# Solder_practice.net
KiCad netlist of a schematic drawn in EasyEDA
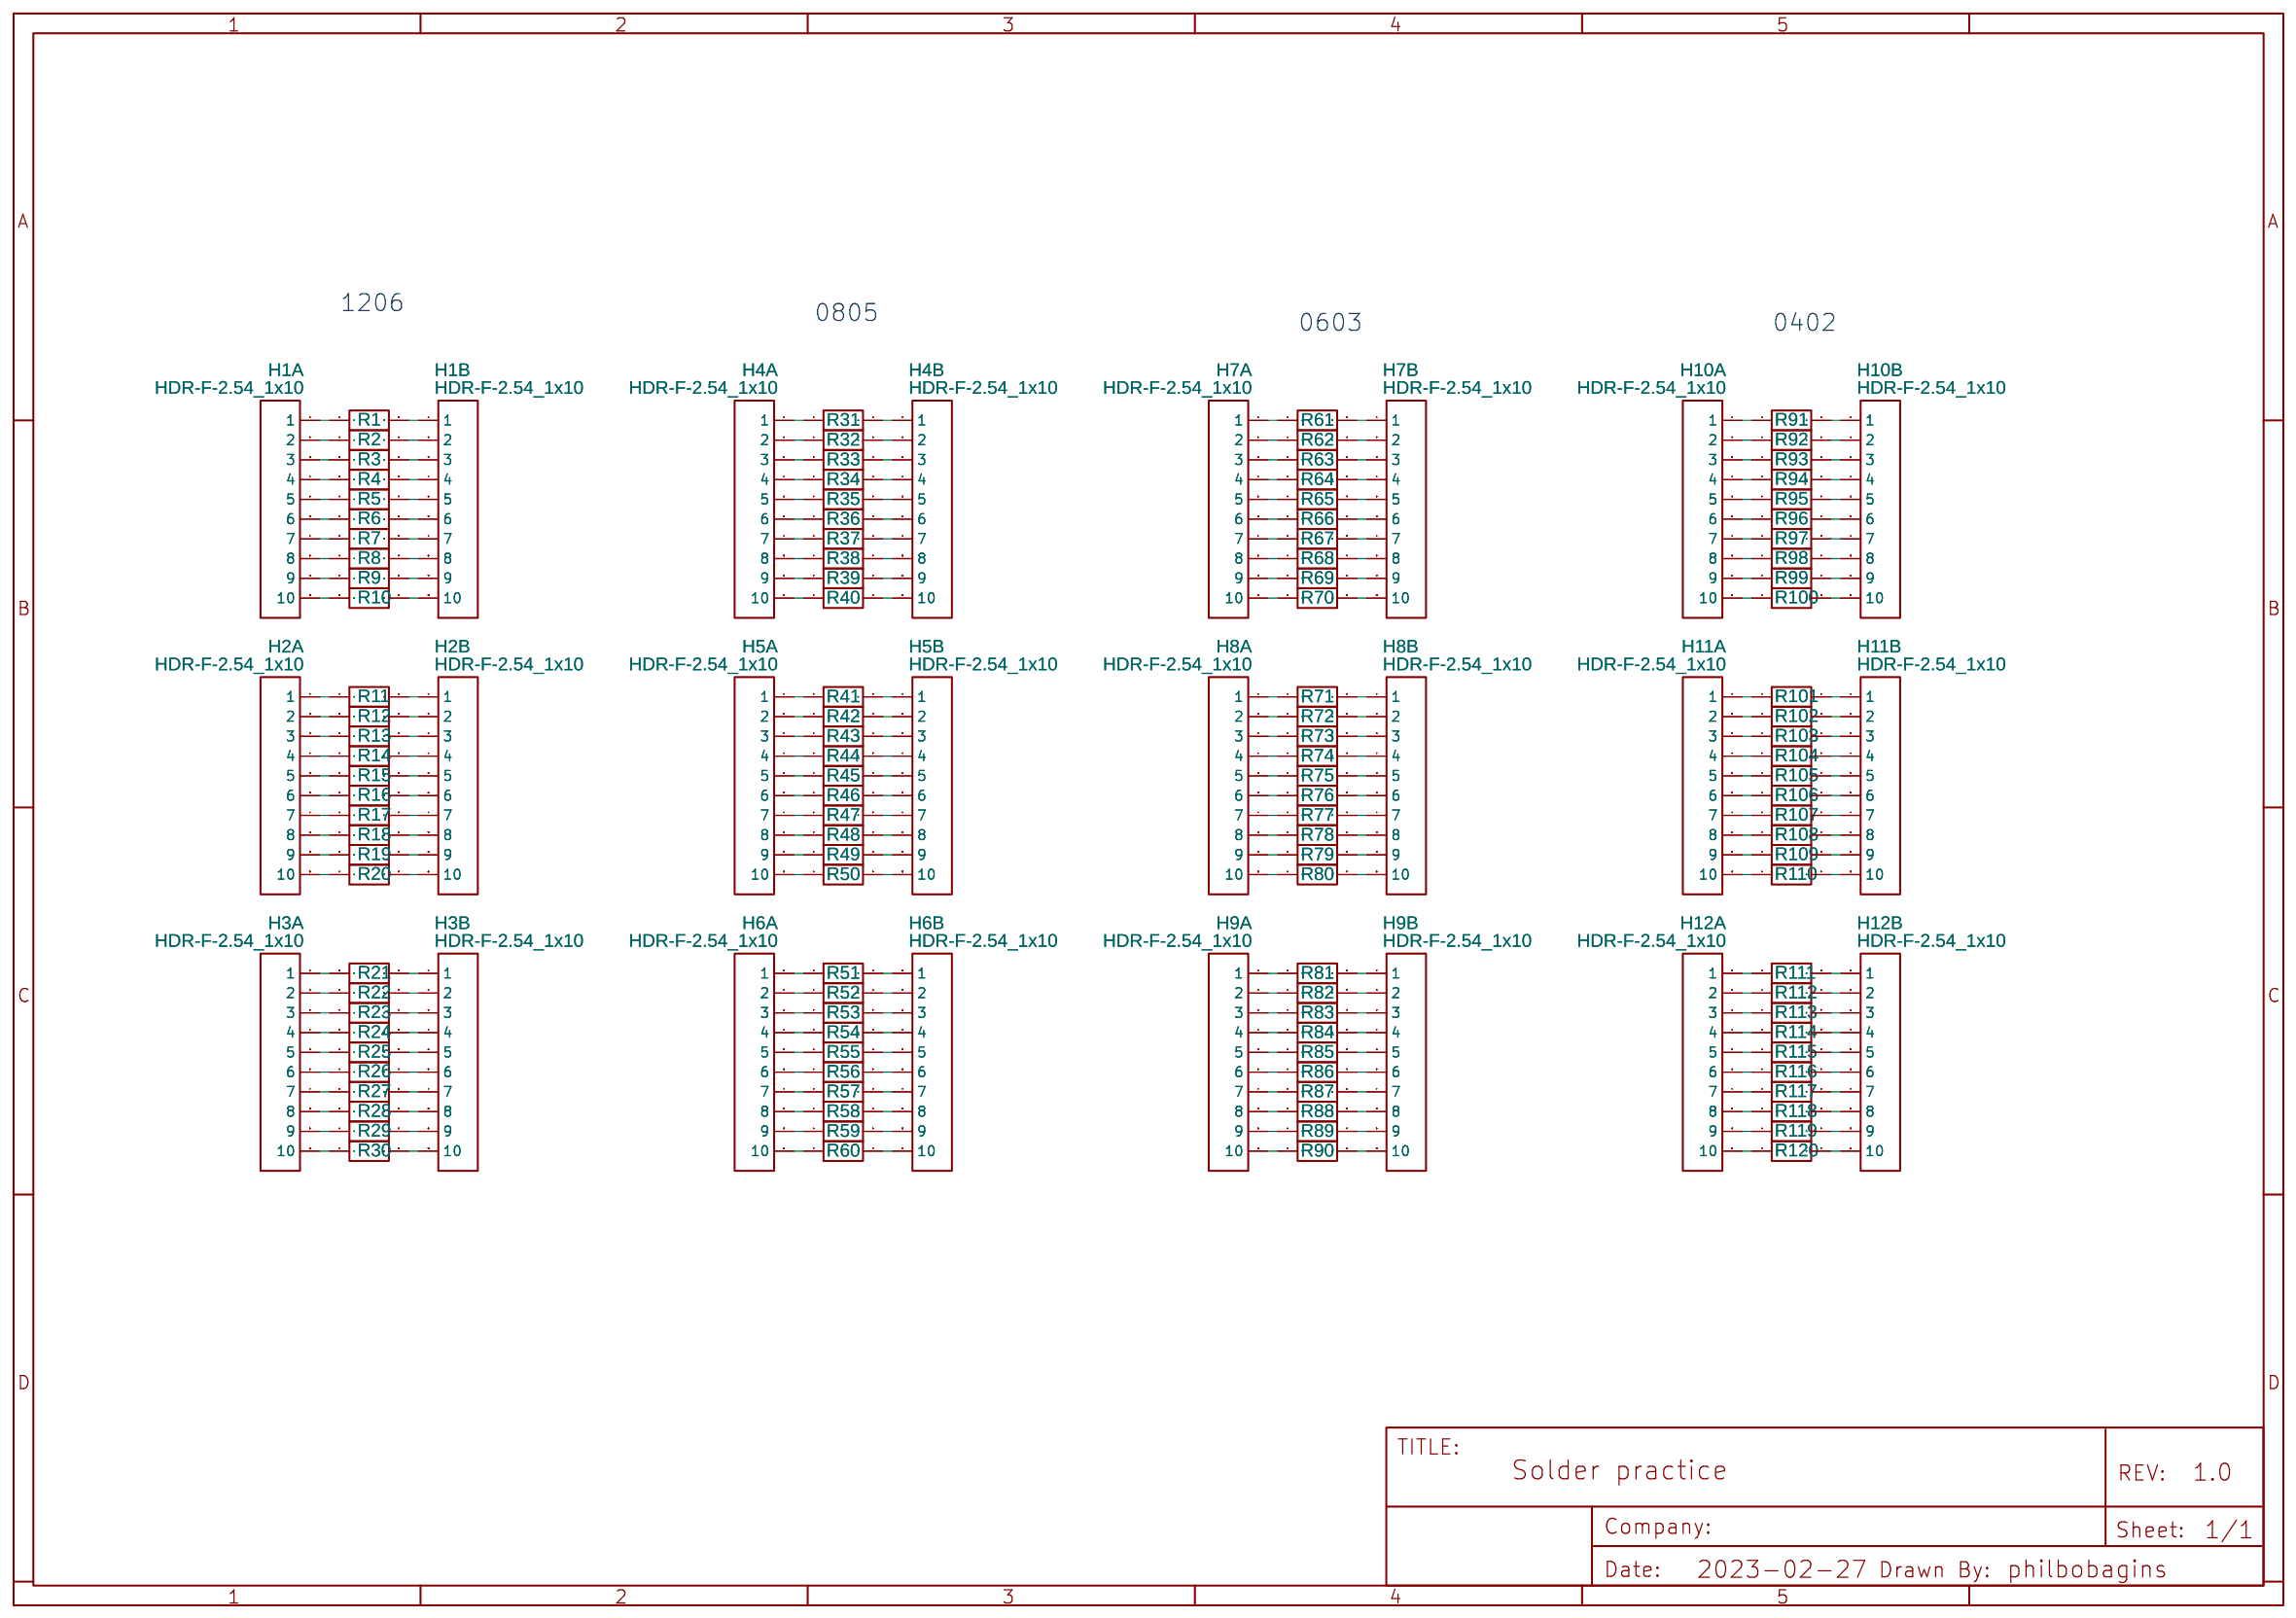
[diagram p0: schematic sheet]

(export (version "E")
  (design (tool "Eeschema 10.0.6"))
  (components
    (comp (ref "H1A")
      (value "HDR-F-2.54_1x10")
      (fields (field (name "BOM_Supplier Part") "C35445"))
      (libsource (lib "") (part "HDR-F-2.54_1x10"))
    )
    (comp (ref "H1B")
      (value "HDR-F-2.54_1x10")
      (fields (field (name "BOM_Supplier Part") "C35445"))
      (libsource (lib "") (part "HDR-F-2.54_1x10_20"))
    )
    (comp (ref "H2A")
      (value "HDR-F-2.54_1x10")
      (fields (field (name "BOM_Supplier Part") "C35445"))
      (libsource (lib "") (part "HDR-F-2.54_1x10_6"))
    )
    (comp (ref "H2B")
      (value "HDR-F-2.54_1x10")
      (fields (field (name "BOM_Supplier Part") "C35445"))
      (libsource (lib "") (part "HDR-F-2.54_1x10_19"))
    )
    (comp (ref "H3A")
      (value "HDR-F-2.54_1x10")
      (fields (field (name "BOM_Supplier Part") "C35445"))
      (libsource (lib "") (part "HDR-F-2.54_1x10_1"))
    )
    (comp (ref "H3B")
      (value "HDR-F-2.54_1x10")
      (fields (field (name "BOM_Supplier Part") "C35445"))
      (libsource (lib "") (part "HDR-F-2.54_1x10_8"))
    )
    (comp (ref "H4A")
      (value "HDR-F-2.54_1x10")
      (fields (field (name "BOM_Supplier Part") "C35445"))
      (libsource (lib "") (part "HDR-F-2.54_1x10_2"))
    )
    (comp (ref "H4B")
      (value "HDR-F-2.54_1x10")
      (fields (field (name "BOM_Supplier Part") "C35445"))
      (libsource (lib "") (part "HDR-F-2.54_1x10_16"))
    )
    (comp (ref "H5A")
      (value "HDR-F-2.54_1x10")
      (fields (field (name "BOM_Supplier Part") "C35445"))
      (libsource (lib "") (part "HDR-F-2.54_1x10_4"))
    )
    (comp (ref "H5B")
      (value "HDR-F-2.54_1x10")
      (fields (field (name "BOM_Supplier Part") "C35445"))
      (libsource (lib "") (part "HDR-F-2.54_1x10_11"))
    )
    (comp (ref "H6A")
      (value "HDR-F-2.54_1x10")
      (fields (field (name "BOM_Supplier Part") "C35445"))
      (libsource (lib "") (part "HDR-F-2.54_1x10_12"))
    )
    (comp (ref "H6B")
      (value "HDR-F-2.54_1x10")
      (fields (field (name "BOM_Supplier Part") "C35445"))
      (libsource (lib "") (part "HDR-F-2.54_1x10_22"))
    )
    (comp (ref "H7A")
      (value "HDR-F-2.54_1x10")
      (fields (field (name "BOM_Supplier Part") "C35445"))
      (libsource (lib "") (part "HDR-F-2.54_1x10_14"))
    )
    (comp (ref "H7B")
      (value "HDR-F-2.54_1x10")
      (fields (field (name "BOM_Supplier Part") "C35445"))
      (libsource (lib "") (part "HDR-F-2.54_1x10_17"))
    )
    (comp (ref "H8A")
      (value "HDR-F-2.54_1x10")
      (fields (field (name "BOM_Supplier Part") "C35445"))
      (libsource (lib "") (part "HDR-F-2.54_1x10_15"))
    )
    (comp (ref "H8B")
      (value "HDR-F-2.54_1x10")
      (fields (field (name "BOM_Supplier Part") "C35445"))
      (libsource (lib "") (part "HDR-F-2.54_1x10_21"))
    )
    (comp (ref "H9A")
      (value "HDR-F-2.54_1x10")
      (fields (field (name "BOM_Supplier Part") "C35445"))
      (libsource (lib "") (part "HDR-F-2.54_1x10_5"))
    )
    (comp (ref "H9B")
      (value "HDR-F-2.54_1x10")
      (fields (field (name "BOM_Supplier Part") "C35445"))
      (libsource (lib "") (part "HDR-F-2.54_1x10_13"))
    )
    (comp (ref "H10A")
      (value "HDR-F-2.54_1x10")
      (fields (field (name "BOM_Supplier Part") "C35445"))
      (libsource (lib "") (part "HDR-F-2.54_1x10_23"))
    )
    (comp (ref "H10B")
      (value "HDR-F-2.54_1x10")
      (fields (field (name "BOM_Supplier Part") "C35445"))
      (libsource (lib "") (part "HDR-F-2.54_1x10_7"))
    )
    (comp (ref "H11A")
      (value "HDR-F-2.54_1x10")
      (fields (field (name "BOM_Supplier Part") "C35445"))
      (libsource (lib "") (part "HDR-F-2.54_1x10_3"))
    )
    (comp (ref "H11B")
      (value "HDR-F-2.54_1x10")
      (fields (field (name "BOM_Supplier Part") "C35445"))
      (libsource (lib "") (part "HDR-F-2.54_1x10_10"))
    )
    (comp (ref "H12A")
      (value "HDR-F-2.54_1x10")
      (fields (field (name "BOM_Supplier Part") "C35445"))
      (libsource (lib "") (part "HDR-F-2.54_1x10_9"))
    )
    (comp (ref "H12B")
      (value "HDR-F-2.54_1x10")
      (fields (field (name "BOM_Supplier Part") "C35445"))
      (libsource (lib "") (part "HDR-F-2.54_1x10_18"))
    )
    (comp (ref "R1") (value "1k") (libsource (lib "") (part "R_1206_EU")))
    (comp (ref "R2") (value "1k") (libsource (lib "") (part "R_1206_EU")))
    (comp (ref "R3") (value "1k") (libsource (lib "") (part "R_1206_EU")))
    (comp (ref "R4") (value "1k") (libsource (lib "") (part "R_1206_EU")))
    (comp (ref "R5") (value "1k") (libsource (lib "") (part "R_1206_EU")))
    (comp (ref "R6") (value "1k") (libsource (lib "") (part "R_1206_EU")))
    (comp (ref "R7") (value "1k") (libsource (lib "") (part "R_1206_EU")))
    (comp (ref "R8") (value "1k") (libsource (lib "") (part "R_1206_EU")))
    (comp (ref "R9") (value "1k") (libsource (lib "") (part "R_1206_EU")))
    (comp (ref "R10") (value "1k") (libsource (lib "") (part "R_1206_EU")))
    (comp (ref "R11") (value "1k") (libsource (lib "") (part "R_1206_EU")))
    (comp (ref "R12") (value "1k") (libsource (lib "") (part "R_1206_EU")))
    (comp (ref "R13") (value "1k") (libsource (lib "") (part "R_1206_EU")))
    (comp (ref "R14") (value "1k") (libsource (lib "") (part "R_1206_EU")))
    (comp (ref "R15") (value "1k") (libsource (lib "") (part "R_1206_EU")))
    (comp (ref "R16") (value "1k") (libsource (lib "") (part "R_1206_EU")))
    (comp (ref "R17") (value "1k") (libsource (lib "") (part "R_1206_EU")))
    (comp (ref "R18") (value "1k") (libsource (lib "") (part "R_1206_EU")))
    (comp (ref "R19") (value "1k") (libsource (lib "") (part "R_1206_EU")))
    (comp (ref "R20") (value "1k") (libsource (lib "") (part "R_1206_EU")))
    (comp (ref "R21") (value "1k") (libsource (lib "") (part "R_1206_EU")))
    (comp (ref "R22") (value "1k") (libsource (lib "") (part "R_1206_EU")))
    (comp (ref "R23") (value "1k") (libsource (lib "") (part "R_1206_EU")))
    (comp (ref "R24") (value "1k") (libsource (lib "") (part "R_1206_EU")))
    (comp (ref "R25") (value "1k") (libsource (lib "") (part "R_1206_EU")))
    (comp (ref "R26") (value "1k") (libsource (lib "") (part "R_1206_EU")))
    (comp (ref "R27") (value "1k") (libsource (lib "") (part "R_1206_EU")))
    (comp (ref "R28") (value "1k") (libsource (lib "") (part "R_1206_EU")))
    (comp (ref "R29") (value "1k") (libsource (lib "") (part "R_1206_EU")))
    (comp (ref "R30") (value "1k") (libsource (lib "") (part "R_1206_EU")))
    (comp (ref "R31") (value "1k") (libsource (lib "") (part "R_0805_EU")))
    (comp (ref "R32") (value "1k") (libsource (lib "") (part "R_0805_EU")))
    (comp (ref "R33") (value "1k") (libsource (lib "") (part "R_0805_EU")))
    (comp (ref "R34") (value "1k") (libsource (lib "") (part "R_0805_EU")))
    (comp (ref "R35") (value "1k") (libsource (lib "") (part "R_0805_EU")))
    (comp (ref "R36") (value "1k") (libsource (lib "") (part "R_0805_EU")))
    (comp (ref "R37") (value "1k") (libsource (lib "") (part "R_0805_EU")))
    (comp (ref "R38") (value "1k") (libsource (lib "") (part "R_0805_EU")))
    (comp (ref "R39") (value "1k") (libsource (lib "") (part "R_0805_EU")))
    (comp (ref "R40") (value "1k") (libsource (lib "") (part "R_0805_EU")))
    (comp (ref "R41") (value "1k") (libsource (lib "") (part "R_0805_EU")))
    (comp (ref "R42") (value "1k") (libsource (lib "") (part "R_0805_EU")))
    (comp (ref "R43") (value "1k") (libsource (lib "") (part "R_0805_EU")))
    (comp (ref "R44") (value "1k") (libsource (lib "") (part "R_0805_EU")))
    (comp (ref "R45") (value "1k") (libsource (lib "") (part "R_0805_EU")))
    (comp (ref "R46") (value "1k") (libsource (lib "") (part "R_0805_EU")))
    (comp (ref "R47") (value "1k") (libsource (lib "") (part "R_0805_EU")))
    (comp (ref "R48") (value "1k") (libsource (lib "") (part "R_0805_EU")))
    (comp (ref "R49") (value "1k") (libsource (lib "") (part "R_0805_EU")))
    (comp (ref "R50") (value "1k") (libsource (lib "") (part "R_0805_EU")))
    (comp (ref "R51") (value "1k") (libsource (lib "") (part "R_0805_EU")))
    (comp (ref "R52") (value "1k") (libsource (lib "") (part "R_0805_EU")))
    (comp (ref "R53") (value "1k") (libsource (lib "") (part "R_0805_EU")))
    (comp (ref "R54") (value "1k") (libsource (lib "") (part "R_0805_EU")))
    (comp (ref "R55") (value "1k") (libsource (lib "") (part "R_0805_EU")))
    (comp (ref "R56") (value "1k") (libsource (lib "") (part "R_0805_EU")))
    (comp (ref "R57") (value "1k") (libsource (lib "") (part "R_0805_EU")))
    (comp (ref "R58") (value "1k") (libsource (lib "") (part "R_0805_EU")))
    (comp (ref "R59") (value "1k") (libsource (lib "") (part "R_0805_EU")))
    (comp (ref "R60") (value "1k") (libsource (lib "") (part "R_0805_EU")))
    (comp (ref "R61") (value "1k") (libsource (lib "") (part "R_0603_EU")))
    (comp (ref "R62") (value "1k") (libsource (lib "") (part "R_0603_EU")))
    (comp (ref "R63") (value "1k") (libsource (lib "") (part "R_0603_EU")))
    (comp (ref "R64") (value "1k") (libsource (lib "") (part "R_0603_EU")))
    (comp (ref "R65") (value "1k") (libsource (lib "") (part "R_0603_EU")))
    (comp (ref "R66") (value "1k") (libsource (lib "") (part "R_0603_EU")))
    (comp (ref "R67") (value "1k") (libsource (lib "") (part "R_0603_EU")))
    (comp (ref "R68") (value "1k") (libsource (lib "") (part "R_0603_EU")))
    (comp (ref "R69") (value "1k") (libsource (lib "") (part "R_0603_EU")))
    (comp (ref "R70") (value "1k") (libsource (lib "") (part "R_0603_EU")))
    (comp (ref "R71") (value "1k") (libsource (lib "") (part "R_0603_EU")))
    (comp (ref "R72") (value "1k") (libsource (lib "") (part "R_0603_EU")))
    (comp (ref "R73") (value "1k") (libsource (lib "") (part "R_0603_EU")))
    (comp (ref "R74") (value "1k") (libsource (lib "") (part "R_0603_EU")))
    (comp (ref "R75") (value "1k") (libsource (lib "") (part "R_0603_EU")))
    (comp (ref "R76") (value "1k") (libsource (lib "") (part "R_0603_EU")))
    (comp (ref "R77") (value "1k") (libsource (lib "") (part "R_0603_EU")))
    (comp (ref "R78") (value "1k") (libsource (lib "") (part "R_0603_EU")))
    (comp (ref "R79") (value "1k") (libsource (lib "") (part "R_0603_EU")))
    (comp (ref "R80") (value "1k") (libsource (lib "") (part "R_0603_EU")))
    (comp (ref "R81") (value "1k") (libsource (lib "") (part "R_0603_EU")))
    (comp (ref "R82") (value "1k") (libsource (lib "") (part "R_0603_EU")))
    (comp (ref "R83") (value "1k") (libsource (lib "") (part "R_0603_EU")))
    (comp (ref "R84") (value "1k") (libsource (lib "") (part "R_0603_EU")))
    (comp (ref "R85") (value "1k") (libsource (lib "") (part "R_0603_EU")))
    (comp (ref "R86") (value "1k") (libsource (lib "") (part "R_0603_EU")))
    (comp (ref "R87") (value "1k") (libsource (lib "") (part "R_0603_EU")))
    (comp (ref "R88") (value "1k") (libsource (lib "") (part "R_0603_EU")))
    (comp (ref "R89") (value "1k") (libsource (lib "") (part "R_0603_EU")))
    (comp (ref "R90") (value "1k") (libsource (lib "") (part "R_0603_EU")))
    (comp (ref "R91") (value "1k") (libsource (lib "") (part "R_0402_EU")))
    (comp (ref "R92") (value "1k") (libsource (lib "") (part "R_0402_EU")))
    (comp (ref "R93") (value "1k") (libsource (lib "") (part "R_0402_EU")))
    (comp (ref "R94") (value "1k") (libsource (lib "") (part "R_0402_EU")))
    (comp (ref "R95") (value "1k") (libsource (lib "") (part "R_0402_EU")))
    (comp (ref "R96") (value "1k") (libsource (lib "") (part "R_0402_EU")))
    (comp (ref "R97") (value "1k") (libsource (lib "") (part "R_0402_EU")))
    (comp (ref "R98") (value "1k") (libsource (lib "") (part "R_0402_EU")))
    (comp (ref "R99") (value "1k") (libsource (lib "") (part "R_0402_EU")))
    (comp (ref "R100") (value "1k") (libsource (lib "") (part "R_0402_EU")))
    (comp (ref "R101") (value "1k") (libsource (lib "") (part "R_0402_EU")))
    (comp (ref "R102") (value "1k") (libsource (lib "") (part "R_0402_EU")))
    (comp (ref "R103") (value "1k") (libsource (lib "") (part "R_0402_EU")))
    (comp (ref "R104") (value "1k") (libsource (lib "") (part "R_0402_EU")))
    (comp (ref "R105") (value "1k") (libsource (lib "") (part "R_0402_EU")))
    (comp (ref "R106") (value "1k") (libsource (lib "") (part "R_0402_EU")))
    (comp (ref "R107") (value "1k") (libsource (lib "") (part "R_0402_EU")))
    (comp (ref "R108") (value "1k") (libsource (lib "") (part "R_0402_EU")))
    (comp (ref "R109") (value "1k") (libsource (lib "") (part "R_0402_EU")))
    (comp (ref "R110") (value "1k") (libsource (lib "") (part "R_0402_EU")))
    (comp (ref "R111") (value "1k") (libsource (lib "") (part "R_0402_EU")))
    (comp (ref "R112") (value "1k") (libsource (lib "") (part "R_0402_EU")))
    (comp (ref "R113") (value "1k") (libsource (lib "") (part "R_0402_EU")))
    (comp (ref "R114") (value "1k") (libsource (lib "") (part "R_0402_EU")))
    (comp (ref "R115") (value "1k") (libsource (lib "") (part "R_0402_EU")))
    (comp (ref "R116") (value "1k") (libsource (lib "") (part "R_0402_EU")))
    (comp (ref "R117") (value "1k") (libsource (lib "") (part "R_0402_EU")))
    (comp (ref "R118") (value "1k") (libsource (lib "") (part "R_0402_EU")))
    (comp (ref "R119") (value "1k") (libsource (lib "") (part "R_0402_EU")))
    (comp (ref "R120") (value "1k") (libsource (lib "") (part "R_0402_EU")))
  )
  (nets
    (net (code "1") (name "Net-(H1A-Pad1)") (class "Default")
      (node (ref "H1A") (pin "1") (pinfunction "1_1") (pintype "unspecified"))
      (node (ref "R1") (pin "1") (pinfunction "1_1") (pintype "unspecified"))
    )
    (net (code "2") (name "Net-(H1A-Pad2)") (class "Default")
      (node (ref "H1A") (pin "2") (pinfunction "2_2") (pintype "unspecified"))
      (node (ref "R2") (pin "1") (pinfunction "1_1") (pintype "unspecified"))
    )
    (net (code "3") (name "Net-(H1A-Pad3)") (class "Default")
      (node (ref "H1A") (pin "3") (pinfunction "3_3") (pintype "unspecified"))
      (node (ref "R3") (pin "1") (pinfunction "1_1") (pintype "unspecified"))
    )
    (net (code "4") (name "Net-(H1A-Pad4)") (class "Default")
      (node (ref "H1A") (pin "4") (pinfunction "4_4") (pintype "unspecified"))
      (node (ref "R4") (pin "1") (pinfunction "1_1") (pintype "unspecified"))
    )
    (net (code "5") (name "Net-(H1A-Pad5)") (class "Default")
      (node (ref "H1A") (pin "5") (pinfunction "5_5") (pintype "unspecified"))
      (node (ref "R5") (pin "1") (pinfunction "1_1") (pintype "unspecified"))
    )
    (net (code "6") (name "Net-(H1A-Pad6)") (class "Default")
      (node (ref "H1A") (pin "6") (pinfunction "6_6") (pintype "unspecified"))
      (node (ref "R6") (pin "1") (pinfunction "1_1") (pintype "unspecified"))
    )
    (net (code "7") (name "Net-(H1A-Pad7)") (class "Default")
      (node (ref "H1A") (pin "7") (pinfunction "7_7") (pintype "unspecified"))
      (node (ref "R7") (pin "1") (pinfunction "1_1") (pintype "unspecified"))
    )
    (net (code "8") (name "Net-(H1A-Pad8)") (class "Default")
      (node (ref "H1A") (pin "8") (pinfunction "8_8") (pintype "unspecified"))
      (node (ref "R8") (pin "1") (pinfunction "1_1") (pintype "unspecified"))
    )
    (net (code "9") (name "Net-(H1A-Pad9)") (class "Default")
      (node (ref "H1A") (pin "9") (pinfunction "9_9") (pintype "unspecified"))
      (node (ref "R9") (pin "1") (pinfunction "1_1") (pintype "unspecified"))
    )
    (net (code "10") (name "Net-(H1A-Pad10)") (class "Default")
      (node (ref "H1A") (pin "10") (pinfunction "10_10") (pintype "unspecified"))
      (node (ref "R10") (pin "1") (pinfunction "1_1") (pintype "unspecified"))
    )
    (net (code "11") (name "Net-(H1B-Pad1)") (class "Default")
      (node (ref "H1B") (pin "1") (pinfunction "1_1") (pintype "unspecified"))
      (node (ref "R1") (pin "2") (pinfunction "2_2") (pintype "unspecified"))
    )
    (net (code "12") (name "Net-(H1B-Pad2)") (class "Default")
      (node (ref "H1B") (pin "2") (pinfunction "2_2") (pintype "unspecified"))
      (node (ref "R2") (pin "2") (pinfunction "2_2") (pintype "unspecified"))
    )
    (net (code "13") (name "Net-(H1B-Pad3)") (class "Default")
      (node (ref "H1B") (pin "3") (pinfunction "3_3") (pintype "unspecified"))
      (node (ref "R3") (pin "2") (pinfunction "2_2") (pintype "unspecified"))
    )
    (net (code "14") (name "Net-(H1B-Pad4)") (class "Default")
      (node (ref "H1B") (pin "4") (pinfunction "4_4") (pintype "unspecified"))
      (node (ref "R4") (pin "2") (pinfunction "2_2") (pintype "unspecified"))
    )
    (net (code "15") (name "Net-(H1B-Pad5)") (class "Default")
      (node (ref "H1B") (pin "5") (pinfunction "5_5") (pintype "unspecified"))
      (node (ref "R5") (pin "2") (pinfunction "2_2") (pintype "unspecified"))
    )
    (net (code "16") (name "Net-(H1B-Pad6)") (class "Default")
      (node (ref "H1B") (pin "6") (pinfunction "6_6") (pintype "unspecified"))
      (node (ref "R6") (pin "2") (pinfunction "2_2") (pintype "unspecified"))
    )
    (net (code "17") (name "Net-(H1B-Pad7)") (class "Default")
      (node (ref "H1B") (pin "7") (pinfunction "7_7") (pintype "unspecified"))
      (node (ref "R7") (pin "2") (pinfunction "2_2") (pintype "unspecified"))
    )
    (net (code "18") (name "Net-(H1B-Pad8)") (class "Default")
      (node (ref "H1B") (pin "8") (pinfunction "8_8") (pintype "unspecified"))
      (node (ref "R8") (pin "2") (pinfunction "2_2") (pintype "unspecified"))
    )
    (net (code "19") (name "Net-(H1B-Pad9)") (class "Default")
      (node (ref "H1B") (pin "9") (pinfunction "9_9") (pintype "unspecified"))
      (node (ref "R9") (pin "2") (pinfunction "2_2") (pintype "unspecified"))
    )
    (net (code "20") (name "Net-(H1B-Pad10)") (class "Default")
      (node (ref "H1B") (pin "10") (pinfunction "10_10") (pintype "unspecified"))
      (node (ref "R10") (pin "2") (pinfunction "2_2") (pintype "unspecified"))
    )
    (net (code "21") (name "Net-(H2A-Pad1)") (class "Default")
      (node (ref "H2A") (pin "1") (pinfunction "1_1") (pintype "unspecified"))
      (node (ref "R11") (pin "1") (pinfunction "1_1") (pintype "unspecified"))
    )
    (net (code "22") (name "Net-(H2A-Pad2)") (class "Default")
      (node (ref "H2A") (pin "2") (pinfunction "2_2") (pintype "unspecified"))
      (node (ref "R12") (pin "1") (pinfunction "1_1") (pintype "unspecified"))
    )
    (net (code "23") (name "Net-(H2A-Pad3)") (class "Default")
      (node (ref "H2A") (pin "3") (pinfunction "3_3") (pintype "unspecified"))
      (node (ref "R13") (pin "1") (pinfunction "1_1") (pintype "unspecified"))
    )
    (net (code "24") (name "Net-(H2A-Pad4)") (class "Default")
      (node (ref "H2A") (pin "4") (pinfunction "4_4") (pintype "unspecified"))
      (node (ref "R14") (pin "1") (pinfunction "1_1") (pintype "unspecified"))
    )
    (net (code "25") (name "Net-(H2A-Pad5)") (class "Default")
      (node (ref "H2A") (pin "5") (pinfunction "5_5") (pintype "unspecified"))
      (node (ref "R15") (pin "1") (pinfunction "1_1") (pintype "unspecified"))
    )
    (net (code "26") (name "Net-(H2A-Pad6)") (class "Default")
      (node (ref "H2A") (pin "6") (pinfunction "6_6") (pintype "unspecified"))
      (node (ref "R16") (pin "1") (pinfunction "1_1") (pintype "unspecified"))
    )
    (net (code "27") (name "Net-(H2A-Pad7)") (class "Default")
      (node (ref "H2A") (pin "7") (pinfunction "7_7") (pintype "unspecified"))
      (node (ref "R17") (pin "1") (pinfunction "1_1") (pintype "unspecified"))
    )
    (net (code "28") (name "Net-(H2A-Pad8)") (class "Default")
      (node (ref "H2A") (pin "8") (pinfunction "8_8") (pintype "unspecified"))
      (node (ref "R18") (pin "1") (pinfunction "1_1") (pintype "unspecified"))
    )
    (net (code "29") (name "Net-(H2A-Pad9)") (class "Default")
      (node (ref "H2A") (pin "9") (pinfunction "9_9") (pintype "unspecified"))
      (node (ref "R19") (pin "1") (pinfunction "1_1") (pintype "unspecified"))
    )
    (net (code "30") (name "Net-(H2A-Pad10)") (class "Default")
      (node (ref "H2A") (pin "10") (pinfunction "10_10") (pintype "unspecified"))
      (node (ref "R20") (pin "1") (pinfunction "1_1") (pintype "unspecified"))
    )
    (net (code "31") (name "Net-(H2B-Pad1)") (class "Default")
      (node (ref "H2B") (pin "1") (pinfunction "1_1") (pintype "unspecified"))
      (node (ref "R11") (pin "2") (pinfunction "2_2") (pintype "unspecified"))
    )
    (net (code "32") (name "Net-(H2B-Pad2)") (class "Default")
      (node (ref "H2B") (pin "2") (pinfunction "2_2") (pintype "unspecified"))
      (node (ref "R12") (pin "2") (pinfunction "2_2") (pintype "unspecified"))
    )
    (net (code "33") (name "Net-(H2B-Pad3)") (class "Default")
      (node (ref "H2B") (pin "3") (pinfunction "3_3") (pintype "unspecified"))
      (node (ref "R13") (pin "2") (pinfunction "2_2") (pintype "unspecified"))
    )
    (net (code "34") (name "Net-(H2B-Pad4)") (class "Default")
      (node (ref "H2B") (pin "4") (pinfunction "4_4") (pintype "unspecified"))
      (node (ref "R14") (pin "2") (pinfunction "2_2") (pintype "unspecified"))
    )
    (net (code "35") (name "Net-(H2B-Pad5)") (class "Default")
      (node (ref "H2B") (pin "5") (pinfunction "5_5") (pintype "unspecified"))
      (node (ref "R15") (pin "2") (pinfunction "2_2") (pintype "unspecified"))
    )
    (net (code "36") (name "Net-(H2B-Pad6)") (class "Default")
      (node (ref "H2B") (pin "6") (pinfunction "6_6") (pintype "unspecified"))
      (node (ref "R16") (pin "2") (pinfunction "2_2") (pintype "unspecified"))
    )
    (net (code "37") (name "Net-(H2B-Pad7)") (class "Default")
      (node (ref "H2B") (pin "7") (pinfunction "7_7") (pintype "unspecified"))
      (node (ref "R17") (pin "2") (pinfunction "2_2") (pintype "unspecified"))
    )
    (net (code "38") (name "Net-(H2B-Pad8)") (class "Default")
      (node (ref "H2B") (pin "8") (pinfunction "8_8") (pintype "unspecified"))
      (node (ref "R18") (pin "2") (pinfunction "2_2") (pintype "unspecified"))
    )
    (net (code "39") (name "Net-(H2B-Pad9)") (class "Default")
      (node (ref "H2B") (pin "9") (pinfunction "9_9") (pintype "unspecified"))
      (node (ref "R19") (pin "2") (pinfunction "2_2") (pintype "unspecified"))
    )
    (net (code "40") (name "Net-(H2B-Pad10)") (class "Default")
      (node (ref "H2B") (pin "10") (pinfunction "10_10") (pintype "unspecified"))
      (node (ref "R20") (pin "2") (pinfunction "2_2") (pintype "unspecified"))
    )
    (net (code "41") (name "Net-(H3A-Pad1)") (class "Default")
      (node (ref "H3A") (pin "1") (pinfunction "1_1") (pintype "unspecified"))
      (node (ref "R21") (pin "1") (pinfunction "1_1") (pintype "unspecified"))
    )
    (net (code "42") (name "Net-(H3A-Pad2)") (class "Default")
      (node (ref "H3A") (pin "2") (pinfunction "2_2") (pintype "unspecified"))
      (node (ref "R22") (pin "1") (pinfunction "1_1") (pintype "unspecified"))
    )
    (net (code "43") (name "Net-(H3A-Pad3)") (class "Default")
      (node (ref "H3A") (pin "3") (pinfunction "3_3") (pintype "unspecified"))
      (node (ref "R23") (pin "1") (pinfunction "1_1") (pintype "unspecified"))
    )
    (net (code "44") (name "Net-(H3A-Pad4)") (class "Default")
      (node (ref "H3A") (pin "4") (pinfunction "4_4") (pintype "unspecified"))
      (node (ref "R24") (pin "1") (pinfunction "1_1") (pintype "unspecified"))
    )
    (net (code "45") (name "Net-(H3A-Pad5)") (class "Default")
      (node (ref "H3A") (pin "5") (pinfunction "5_5") (pintype "unspecified"))
      (node (ref "R25") (pin "1") (pinfunction "1_1") (pintype "unspecified"))
    )
    (net (code "46") (name "Net-(H3A-Pad6)") (class "Default")
      (node (ref "H3A") (pin "6") (pinfunction "6_6") (pintype "unspecified"))
      (node (ref "R26") (pin "1") (pinfunction "1_1") (pintype "unspecified"))
    )
    (net (code "47") (name "Net-(H3A-Pad7)") (class "Default")
      (node (ref "H3A") (pin "7") (pinfunction "7_7") (pintype "unspecified"))
      (node (ref "R27") (pin "1") (pinfunction "1_1") (pintype "unspecified"))
    )
    (net (code "48") (name "Net-(H3A-Pad8)") (class "Default")
      (node (ref "H3A") (pin "8") (pinfunction "8_8") (pintype "unspecified"))
      (node (ref "R28") (pin "1") (pinfunction "1_1") (pintype "unspecified"))
    )
    (net (code "49") (name "Net-(H3A-Pad9)") (class "Default")
      (node (ref "H3A") (pin "9") (pinfunction "9_9") (pintype "unspecified"))
      (node (ref "R29") (pin "1") (pinfunction "1_1") (pintype "unspecified"))
    )
    (net (code "50") (name "Net-(H3A-Pad10)") (class "Default")
      (node (ref "H3A") (pin "10") (pinfunction "10_10") (pintype "unspecified"))
      (node (ref "R30") (pin "1") (pinfunction "1_1") (pintype "unspecified"))
    )
    (net (code "51") (name "Net-(H3B-Pad1)") (class "Default")
      (node (ref "H3B") (pin "1") (pinfunction "1_1") (pintype "unspecified"))
      (node (ref "R21") (pin "2") (pinfunction "2_2") (pintype "unspecified"))
    )
    (net (code "52") (name "Net-(H3B-Pad2)") (class "Default")
      (node (ref "H3B") (pin "2") (pinfunction "2_2") (pintype "unspecified"))
      (node (ref "R22") (pin "2") (pinfunction "2_2") (pintype "unspecified"))
    )
    (net (code "53") (name "Net-(H3B-Pad3)") (class "Default")
      (node (ref "H3B") (pin "3") (pinfunction "3_3") (pintype "unspecified"))
      (node (ref "R23") (pin "2") (pinfunction "2_2") (pintype "unspecified"))
    )
    (net (code "54") (name "Net-(H3B-Pad4)") (class "Default")
      (node (ref "H3B") (pin "4") (pinfunction "4_4") (pintype "unspecified"))
      (node (ref "R24") (pin "2") (pinfunction "2_2") (pintype "unspecified"))
    )
    (net (code "55") (name "Net-(H3B-Pad5)") (class "Default")
      (node (ref "H3B") (pin "5") (pinfunction "5_5") (pintype "unspecified"))
      (node (ref "R25") (pin "2") (pinfunction "2_2") (pintype "unspecified"))
    )
    (net (code "56") (name "Net-(H3B-Pad6)") (class "Default")
      (node (ref "H3B") (pin "6") (pinfunction "6_6") (pintype "unspecified"))
      (node (ref "R26") (pin "2") (pinfunction "2_2") (pintype "unspecified"))
    )
    (net (code "57") (name "Net-(H3B-Pad7)") (class "Default")
      (node (ref "H3B") (pin "7") (pinfunction "7_7") (pintype "unspecified"))
      (node (ref "R27") (pin "2") (pinfunction "2_2") (pintype "unspecified"))
    )
    (net (code "58") (name "Net-(H3B-Pad8)") (class "Default")
      (node (ref "H3B") (pin "8") (pinfunction "8_8") (pintype "unspecified"))
      (node (ref "R28") (pin "2") (pinfunction "2_2") (pintype "unspecified"))
    )
    (net (code "59") (name "Net-(H3B-Pad9)") (class "Default")
      (node (ref "H3B") (pin "9") (pinfunction "9_9") (pintype "unspecified"))
      (node (ref "R29") (pin "2") (pinfunction "2_2") (pintype "unspecified"))
    )
    (net (code "60") (name "Net-(H3B-Pad10)") (class "Default")
      (node (ref "H3B") (pin "10") (pinfunction "10_10") (pintype "unspecified"))
      (node (ref "R30") (pin "2") (pinfunction "2_2") (pintype "unspecified"))
    )
    (net (code "61") (name "Net-(H4A-Pad1)") (class "Default")
      (node (ref "H4A") (pin "1") (pinfunction "1_1") (pintype "unspecified"))
      (node (ref "R31") (pin "1") (pinfunction "1_1") (pintype "unspecified"))
    )
    (net (code "62") (name "Net-(H4A-Pad2)") (class "Default")
      (node (ref "H4A") (pin "2") (pinfunction "2_2") (pintype "unspecified"))
      (node (ref "R32") (pin "1") (pinfunction "1_1") (pintype "unspecified"))
    )
    (net (code "63") (name "Net-(H4A-Pad3)") (class "Default")
      (node (ref "H4A") (pin "3") (pinfunction "3_3") (pintype "unspecified"))
      (node (ref "R33") (pin "1") (pinfunction "1_1") (pintype "unspecified"))
    )
    (net (code "64") (name "Net-(H4A-Pad4)") (class "Default")
      (node (ref "H4A") (pin "4") (pinfunction "4_4") (pintype "unspecified"))
      (node (ref "R34") (pin "1") (pinfunction "1_1") (pintype "unspecified"))
    )
    (net (code "65") (name "Net-(H4A-Pad5)") (class "Default")
      (node (ref "H4A") (pin "5") (pinfunction "5_5") (pintype "unspecified"))
      (node (ref "R35") (pin "1") (pinfunction "1_1") (pintype "unspecified"))
    )
    (net (code "66") (name "Net-(H4A-Pad6)") (class "Default")
      (node (ref "H4A") (pin "6") (pinfunction "6_6") (pintype "unspecified"))
      (node (ref "R36") (pin "1") (pinfunction "1_1") (pintype "unspecified"))
    )
    (net (code "67") (name "Net-(H4A-Pad7)") (class "Default")
      (node (ref "H4A") (pin "7") (pinfunction "7_7") (pintype "unspecified"))
      (node (ref "R37") (pin "1") (pinfunction "1_1") (pintype "unspecified"))
    )
    (net (code "68") (name "Net-(H4A-Pad8)") (class "Default")
      (node (ref "H4A") (pin "8") (pinfunction "8_8") (pintype "unspecified"))
      (node (ref "R38") (pin "1") (pinfunction "1_1") (pintype "unspecified"))
    )
    (net (code "69") (name "Net-(H4A-Pad9)") (class "Default")
      (node (ref "H4A") (pin "9") (pinfunction "9_9") (pintype "unspecified"))
      (node (ref "R39") (pin "1") (pinfunction "1_1") (pintype "unspecified"))
    )
    (net (code "70") (name "Net-(H4A-Pad10)") (class "Default")
      (node (ref "H4A") (pin "10") (pinfunction "10_10") (pintype "unspecified"))
      (node (ref "R40") (pin "1") (pinfunction "1_1") (pintype "unspecified"))
    )
    (net (code "71") (name "Net-(H4B-Pad1)") (class "Default")
      (node (ref "H4B") (pin "1") (pinfunction "1_1") (pintype "unspecified"))
      (node (ref "R31") (pin "2") (pinfunction "2_2") (pintype "unspecified"))
    )
    (net (code "72") (name "Net-(H4B-Pad2)") (class "Default")
      (node (ref "H4B") (pin "2") (pinfunction "2_2") (pintype "unspecified"))
      (node (ref "R32") (pin "2") (pinfunction "2_2") (pintype "unspecified"))
    )
    (net (code "73") (name "Net-(H4B-Pad3)") (class "Default")
      (node (ref "H4B") (pin "3") (pinfunction "3_3") (pintype "unspecified"))
      (node (ref "R33") (pin "2") (pinfunction "2_2") (pintype "unspecified"))
    )
    (net (code "74") (name "Net-(H4B-Pad4)") (class "Default")
      (node (ref "H4B") (pin "4") (pinfunction "4_4") (pintype "unspecified"))
      (node (ref "R34") (pin "2") (pinfunction "2_2") (pintype "unspecified"))
    )
    (net (code "75") (name "Net-(H4B-Pad5)") (class "Default")
      (node (ref "H4B") (pin "5") (pinfunction "5_5") (pintype "unspecified"))
      (node (ref "R35") (pin "2") (pinfunction "2_2") (pintype "unspecified"))
    )
    (net (code "76") (name "Net-(H4B-Pad6)") (class "Default")
      (node (ref "H4B") (pin "6") (pinfunction "6_6") (pintype "unspecified"))
      (node (ref "R36") (pin "2") (pinfunction "2_2") (pintype "unspecified"))
    )
    (net (code "77") (name "Net-(H4B-Pad7)") (class "Default")
      (node (ref "H4B") (pin "7") (pinfunction "7_7") (pintype "unspecified"))
      (node (ref "R37") (pin "2") (pinfunction "2_2") (pintype "unspecified"))
    )
    (net (code "78") (name "Net-(H4B-Pad8)") (class "Default")
      (node (ref "H4B") (pin "8") (pinfunction "8_8") (pintype "unspecified"))
      (node (ref "R38") (pin "2") (pinfunction "2_2") (pintype "unspecified"))
    )
    (net (code "79") (name "Net-(H4B-Pad9)") (class "Default")
      (node (ref "H4B") (pin "9") (pinfunction "9_9") (pintype "unspecified"))
      (node (ref "R39") (pin "2") (pinfunction "2_2") (pintype "unspecified"))
    )
    (net (code "80") (name "Net-(H4B-Pad10)") (class "Default")
      (node (ref "H4B") (pin "10") (pinfunction "10_10") (pintype "unspecified"))
      (node (ref "R40") (pin "2") (pinfunction "2_2") (pintype "unspecified"))
    )
    (net (code "81") (name "Net-(H5A-Pad1)") (class "Default")
      (node (ref "H5A") (pin "1") (pinfunction "1_1") (pintype "unspecified"))
      (node (ref "R41") (pin "1") (pinfunction "1_1") (pintype "unspecified"))
    )
    (net (code "82") (name "Net-(H5A-Pad2)") (class "Default")
      (node (ref "H5A") (pin "2") (pinfunction "2_2") (pintype "unspecified"))
      (node (ref "R42") (pin "1") (pinfunction "1_1") (pintype "unspecified"))
    )
    (net (code "83") (name "Net-(H5A-Pad3)") (class "Default")
      (node (ref "H5A") (pin "3") (pinfunction "3_3") (pintype "unspecified"))
      (node (ref "R43") (pin "1") (pinfunction "1_1") (pintype "unspecified"))
    )
    (net (code "84") (name "Net-(H5A-Pad4)") (class "Default")
      (node (ref "H5A") (pin "4") (pinfunction "4_4") (pintype "unspecified"))
      (node (ref "R44") (pin "1") (pinfunction "1_1") (pintype "unspecified"))
    )
    (net (code "85") (name "Net-(H5A-Pad5)") (class "Default")
      (node (ref "H5A") (pin "5") (pinfunction "5_5") (pintype "unspecified"))
      (node (ref "R45") (pin "1") (pinfunction "1_1") (pintype "unspecified"))
    )
    (net (code "86") (name "Net-(H5A-Pad6)") (class "Default")
      (node (ref "H5A") (pin "6") (pinfunction "6_6") (pintype "unspecified"))
      (node (ref "R46") (pin "1") (pinfunction "1_1") (pintype "unspecified"))
    )
    (net (code "87") (name "Net-(H5A-Pad7)") (class "Default")
      (node (ref "H5A") (pin "7") (pinfunction "7_7") (pintype "unspecified"))
      (node (ref "R47") (pin "1") (pinfunction "1_1") (pintype "unspecified"))
    )
    (net (code "88") (name "Net-(H5A-Pad8)") (class "Default")
      (node (ref "H5A") (pin "8") (pinfunction "8_8") (pintype "unspecified"))
      (node (ref "R48") (pin "1") (pinfunction "1_1") (pintype "unspecified"))
    )
    (net (code "89") (name "Net-(H5A-Pad9)") (class "Default")
      (node (ref "H5A") (pin "9") (pinfunction "9_9") (pintype "unspecified"))
      (node (ref "R49") (pin "1") (pinfunction "1_1") (pintype "unspecified"))
    )
    (net (code "90") (name "Net-(H5A-Pad10)") (class "Default")
      (node (ref "H5A") (pin "10") (pinfunction "10_10") (pintype "unspecified"))
      (node (ref "R50") (pin "1") (pinfunction "1_1") (pintype "unspecified"))
    )
    (net (code "91") (name "Net-(H5B-Pad1)") (class "Default")
      (node (ref "H5B") (pin "1") (pinfunction "1_1") (pintype "unspecified"))
      (node (ref "R41") (pin "2") (pinfunction "2_2") (pintype "unspecified"))
    )
    (net (code "92") (name "Net-(H5B-Pad2)") (class "Default")
      (node (ref "H5B") (pin "2") (pinfunction "2_2") (pintype "unspecified"))
      (node (ref "R42") (pin "2") (pinfunction "2_2") (pintype "unspecified"))
    )
    (net (code "93") (name "Net-(H5B-Pad3)") (class "Default")
      (node (ref "H5B") (pin "3") (pinfunction "3_3") (pintype "unspecified"))
      (node (ref "R43") (pin "2") (pinfunction "2_2") (pintype "unspecified"))
    )
    (net (code "94") (name "Net-(H5B-Pad4)") (class "Default")
      (node (ref "H5B") (pin "4") (pinfunction "4_4") (pintype "unspecified"))
      (node (ref "R44") (pin "2") (pinfunction "2_2") (pintype "unspecified"))
    )
    (net (code "95") (name "Net-(H5B-Pad5)") (class "Default")
      (node (ref "H5B") (pin "5") (pinfunction "5_5") (pintype "unspecified"))
      (node (ref "R45") (pin "2") (pinfunction "2_2") (pintype "unspecified"))
    )
    (net (code "96") (name "Net-(H5B-Pad6)") (class "Default")
      (node (ref "H5B") (pin "6") (pinfunction "6_6") (pintype "unspecified"))
      (node (ref "R46") (pin "2") (pinfunction "2_2") (pintype "unspecified"))
    )
    (net (code "97") (name "Net-(H5B-Pad7)") (class "Default")
      (node (ref "H5B") (pin "7") (pinfunction "7_7") (pintype "unspecified"))
      (node (ref "R47") (pin "2") (pinfunction "2_2") (pintype "unspecified"))
    )
    (net (code "98") (name "Net-(H5B-Pad8)") (class "Default")
      (node (ref "H5B") (pin "8") (pinfunction "8_8") (pintype "unspecified"))
      (node (ref "R48") (pin "2") (pinfunction "2_2") (pintype "unspecified"))
    )
    (net (code "99") (name "Net-(H5B-Pad9)") (class "Default")
      (node (ref "H5B") (pin "9") (pinfunction "9_9") (pintype "unspecified"))
      (node (ref "R49") (pin "2") (pinfunction "2_2") (pintype "unspecified"))
    )
    (net (code "100") (name "Net-(H5B-Pad10)") (class "Default")
      (node (ref "H5B") (pin "10") (pinfunction "10_10") (pintype "unspecified"))
      (node (ref "R50") (pin "2") (pinfunction "2_2") (pintype "unspecified"))
    )
    (net (code "101") (name "Net-(H6A-Pad1)") (class "Default")
      (node (ref "H6A") (pin "1") (pinfunction "1_1") (pintype "unspecified"))
      (node (ref "R51") (pin "1") (pinfunction "1_1") (pintype "unspecified"))
    )
    (net (code "102") (name "Net-(H6A-Pad2)") (class "Default")
      (node (ref "H6A") (pin "2") (pinfunction "2_2") (pintype "unspecified"))
      (node (ref "R52") (pin "1") (pinfunction "1_1") (pintype "unspecified"))
    )
    (net (code "103") (name "Net-(H6A-Pad3)") (class "Default")
      (node (ref "H6A") (pin "3") (pinfunction "3_3") (pintype "unspecified"))
      (node (ref "R53") (pin "1") (pinfunction "1_1") (pintype "unspecified"))
    )
    (net (code "104") (name "Net-(H6A-Pad4)") (class "Default")
      (node (ref "H6A") (pin "4") (pinfunction "4_4") (pintype "unspecified"))
      (node (ref "R54") (pin "1") (pinfunction "1_1") (pintype "unspecified"))
    )
    (net (code "105") (name "Net-(H6A-Pad5)") (class "Default")
      (node (ref "H6A") (pin "5") (pinfunction "5_5") (pintype "unspecified"))
      (node (ref "R55") (pin "1") (pinfunction "1_1") (pintype "unspecified"))
    )
    (net (code "106") (name "Net-(H6A-Pad6)") (class "Default")
      (node (ref "H6A") (pin "6") (pinfunction "6_6") (pintype "unspecified"))
      (node (ref "R56") (pin "1") (pinfunction "1_1") (pintype "unspecified"))
    )
    (net (code "107") (name "Net-(H6A-Pad7)") (class "Default")
      (node (ref "H6A") (pin "7") (pinfunction "7_7") (pintype "unspecified"))
      (node (ref "R57") (pin "1") (pinfunction "1_1") (pintype "unspecified"))
    )
    (net (code "108") (name "Net-(H6A-Pad8)") (class "Default")
      (node (ref "H6A") (pin "8") (pinfunction "8_8") (pintype "unspecified"))
      (node (ref "R58") (pin "1") (pinfunction "1_1") (pintype "unspecified"))
    )
    (net (code "109") (name "Net-(H6A-Pad9)") (class "Default")
      (node (ref "H6A") (pin "9") (pinfunction "9_9") (pintype "unspecified"))
      (node (ref "R59") (pin "1") (pinfunction "1_1") (pintype "unspecified"))
    )
    (net (code "110") (name "Net-(H6A-Pad10)") (class "Default")
      (node (ref "H6A") (pin "10") (pinfunction "10_10") (pintype "unspecified"))
      (node (ref "R60") (pin "1") (pinfunction "1_1") (pintype "unspecified"))
    )
    (net (code "111") (name "Net-(H6B-Pad1)") (class "Default")
      (node (ref "H6B") (pin "1") (pinfunction "1_1") (pintype "unspecified"))
      (node (ref "R51") (pin "2") (pinfunction "2_2") (pintype "unspecified"))
    )
    (net (code "112") (name "Net-(H6B-Pad2)") (class "Default")
      (node (ref "H6B") (pin "2") (pinfunction "2_2") (pintype "unspecified"))
      (node (ref "R52") (pin "2") (pinfunction "2_2") (pintype "unspecified"))
    )
    (net (code "113") (name "Net-(H6B-Pad3)") (class "Default")
      (node (ref "H6B") (pin "3") (pinfunction "3_3") (pintype "unspecified"))
      (node (ref "R53") (pin "2") (pinfunction "2_2") (pintype "unspecified"))
    )
    (net (code "114") (name "Net-(H6B-Pad4)") (class "Default")
      (node (ref "H6B") (pin "4") (pinfunction "4_4") (pintype "unspecified"))
      (node (ref "R54") (pin "2") (pinfunction "2_2") (pintype "unspecified"))
    )
    (net (code "115") (name "Net-(H6B-Pad5)") (class "Default")
      (node (ref "H6B") (pin "5") (pinfunction "5_5") (pintype "unspecified"))
      (node (ref "R55") (pin "2") (pinfunction "2_2") (pintype "unspecified"))
    )
    (net (code "116") (name "Net-(H6B-Pad6)") (class "Default")
      (node (ref "H6B") (pin "6") (pinfunction "6_6") (pintype "unspecified"))
      (node (ref "R56") (pin "2") (pinfunction "2_2") (pintype "unspecified"))
    )
    (net (code "117") (name "Net-(H6B-Pad7)") (class "Default")
      (node (ref "H6B") (pin "7") (pinfunction "7_7") (pintype "unspecified"))
      (node (ref "R57") (pin "2") (pinfunction "2_2") (pintype "unspecified"))
    )
    (net (code "118") (name "Net-(H6B-Pad8)") (class "Default")
      (node (ref "H6B") (pin "8") (pinfunction "8_8") (pintype "unspecified"))
      (node (ref "R58") (pin "2") (pinfunction "2_2") (pintype "unspecified"))
    )
    (net (code "119") (name "Net-(H6B-Pad9)") (class "Default")
      (node (ref "H6B") (pin "9") (pinfunction "9_9") (pintype "unspecified"))
      (node (ref "R59") (pin "2") (pinfunction "2_2") (pintype "unspecified"))
    )
    (net (code "120") (name "Net-(H6B-Pad10)") (class "Default")
      (node (ref "H6B") (pin "10") (pinfunction "10_10") (pintype "unspecified"))
      (node (ref "R60") (pin "2") (pinfunction "2_2") (pintype "unspecified"))
    )
    (net (code "121") (name "Net-(H7A-Pad1)") (class "Default")
      (node (ref "H7A") (pin "1") (pinfunction "1_1") (pintype "unspecified"))
      (node (ref "R61") (pin "1") (pinfunction "1_1") (pintype "unspecified"))
    )
    (net (code "122") (name "Net-(H7A-Pad2)") (class "Default")
      (node (ref "H7A") (pin "2") (pinfunction "2_2") (pintype "unspecified"))
      (node (ref "R62") (pin "1") (pinfunction "1_1") (pintype "unspecified"))
    )
    (net (code "123") (name "Net-(H7A-Pad3)") (class "Default")
      (node (ref "H7A") (pin "3") (pinfunction "3_3") (pintype "unspecified"))
      (node (ref "R63") (pin "1") (pinfunction "1_1") (pintype "unspecified"))
    )
    (net (code "124") (name "Net-(H7A-Pad4)") (class "Default")
      (node (ref "H7A") (pin "4") (pinfunction "4_4") (pintype "unspecified"))
      (node (ref "R64") (pin "1") (pinfunction "1_1") (pintype "unspecified"))
    )
    (net (code "125") (name "Net-(H7A-Pad5)") (class "Default")
      (node (ref "H7A") (pin "5") (pinfunction "5_5") (pintype "unspecified"))
      (node (ref "R65") (pin "1") (pinfunction "1_1") (pintype "unspecified"))
    )
    (net (code "126") (name "Net-(H7A-Pad6)") (class "Default")
      (node (ref "H7A") (pin "6") (pinfunction "6_6") (pintype "unspecified"))
      (node (ref "R66") (pin "1") (pinfunction "1_1") (pintype "unspecified"))
    )
    (net (code "127") (name "Net-(H7A-Pad7)") (class "Default")
      (node (ref "H7A") (pin "7") (pinfunction "7_7") (pintype "unspecified"))
      (node (ref "R67") (pin "1") (pinfunction "1_1") (pintype "unspecified"))
    )
    (net (code "128") (name "Net-(H7A-Pad8)") (class "Default")
      (node (ref "H7A") (pin "8") (pinfunction "8_8") (pintype "unspecified"))
      (node (ref "R68") (pin "1") (pinfunction "1_1") (pintype "unspecified"))
    )
    (net (code "129") (name "Net-(H7A-Pad9)") (class "Default")
      (node (ref "H7A") (pin "9") (pinfunction "9_9") (pintype "unspecified"))
      (node (ref "R69") (pin "1") (pinfunction "1_1") (pintype "unspecified"))
    )
    (net (code "130") (name "Net-(H7A-Pad10)") (class "Default")
      (node (ref "H7A") (pin "10") (pinfunction "10_10") (pintype "unspecified"))
      (node (ref "R70") (pin "1") (pinfunction "1_1") (pintype "unspecified"))
    )
    (net (code "131") (name "Net-(H7B-Pad1)") (class "Default")
      (node (ref "H7B") (pin "1") (pinfunction "1_1") (pintype "unspecified"))
      (node (ref "R61") (pin "2") (pinfunction "2_2") (pintype "unspecified"))
    )
    (net (code "132") (name "Net-(H7B-Pad2)") (class "Default")
      (node (ref "H7B") (pin "2") (pinfunction "2_2") (pintype "unspecified"))
      (node (ref "R62") (pin "2") (pinfunction "2_2") (pintype "unspecified"))
    )
    (net (code "133") (name "Net-(H7B-Pad3)") (class "Default")
      (node (ref "H7B") (pin "3") (pinfunction "3_3") (pintype "unspecified"))
      (node (ref "R63") (pin "2") (pinfunction "2_2") (pintype "unspecified"))
    )
    (net (code "134") (name "Net-(H7B-Pad4)") (class "Default")
      (node (ref "H7B") (pin "4") (pinfunction "4_4") (pintype "unspecified"))
      (node (ref "R64") (pin "2") (pinfunction "2_2") (pintype "unspecified"))
    )
    (net (code "135") (name "Net-(H7B-Pad5)") (class "Default")
      (node (ref "H7B") (pin "5") (pinfunction "5_5") (pintype "unspecified"))
      (node (ref "R65") (pin "2") (pinfunction "2_2") (pintype "unspecified"))
    )
    (net (code "136") (name "Net-(H7B-Pad6)") (class "Default")
      (node (ref "H7B") (pin "6") (pinfunction "6_6") (pintype "unspecified"))
      (node (ref "R66") (pin "2") (pinfunction "2_2") (pintype "unspecified"))
    )
    (net (code "137") (name "Net-(H7B-Pad7)") (class "Default")
      (node (ref "H7B") (pin "7") (pinfunction "7_7") (pintype "unspecified"))
      (node (ref "R67") (pin "2") (pinfunction "2_2") (pintype "unspecified"))
    )
    (net (code "138") (name "Net-(H7B-Pad8)") (class "Default")
      (node (ref "H7B") (pin "8") (pinfunction "8_8") (pintype "unspecified"))
      (node (ref "R68") (pin "2") (pinfunction "2_2") (pintype "unspecified"))
    )
    (net (code "139") (name "Net-(H7B-Pad9)") (class "Default")
      (node (ref "H7B") (pin "9") (pinfunction "9_9") (pintype "unspecified"))
      (node (ref "R69") (pin "2") (pinfunction "2_2") (pintype "unspecified"))
    )
    (net (code "140") (name "Net-(H7B-Pad10)") (class "Default")
      (node (ref "H7B") (pin "10") (pinfunction "10_10") (pintype "unspecified"))
      (node (ref "R70") (pin "2") (pinfunction "2_2") (pintype "unspecified"))
    )
    (net (code "141") (name "Net-(H8A-Pad1)") (class "Default")
      (node (ref "H8A") (pin "1") (pinfunction "1_1") (pintype "unspecified"))
      (node (ref "R71") (pin "1") (pinfunction "1_1") (pintype "unspecified"))
    )
    (net (code "142") (name "Net-(H8A-Pad2)") (class "Default")
      (node (ref "H8A") (pin "2") (pinfunction "2_2") (pintype "unspecified"))
      (node (ref "R72") (pin "1") (pinfunction "1_1") (pintype "unspecified"))
    )
    (net (code "143") (name "Net-(H8A-Pad3)") (class "Default")
      (node (ref "H8A") (pin "3") (pinfunction "3_3") (pintype "unspecified"))
      (node (ref "R73") (pin "1") (pinfunction "1_1") (pintype "unspecified"))
    )
    (net (code "144") (name "Net-(H8A-Pad4)") (class "Default")
      (node (ref "H8A") (pin "4") (pinfunction "4_4") (pintype "unspecified"))
      (node (ref "R74") (pin "1") (pinfunction "1_1") (pintype "unspecified"))
    )
    (net (code "145") (name "Net-(H8A-Pad5)") (class "Default")
      (node (ref "H8A") (pin "5") (pinfunction "5_5") (pintype "unspecified"))
      (node (ref "R75") (pin "1") (pinfunction "1_1") (pintype "unspecified"))
    )
    (net (code "146") (name "Net-(H8A-Pad6)") (class "Default")
      (node (ref "H8A") (pin "6") (pinfunction "6_6") (pintype "unspecified"))
      (node (ref "R76") (pin "1") (pinfunction "1_1") (pintype "unspecified"))
    )
    (net (code "147") (name "Net-(H8A-Pad7)") (class "Default")
      (node (ref "H8A") (pin "7") (pinfunction "7_7") (pintype "unspecified"))
      (node (ref "R77") (pin "1") (pinfunction "1_1") (pintype "unspecified"))
    )
    (net (code "148") (name "Net-(H8A-Pad8)") (class "Default")
      (node (ref "H8A") (pin "8") (pinfunction "8_8") (pintype "unspecified"))
      (node (ref "R78") (pin "1") (pinfunction "1_1") (pintype "unspecified"))
    )
    (net (code "149") (name "Net-(H8A-Pad9)") (class "Default")
      (node (ref "H8A") (pin "9") (pinfunction "9_9") (pintype "unspecified"))
      (node (ref "R79") (pin "1") (pinfunction "1_1") (pintype "unspecified"))
    )
    (net (code "150") (name "Net-(H8A-Pad10)") (class "Default")
      (node (ref "H8A") (pin "10") (pinfunction "10_10") (pintype "unspecified"))
      (node (ref "R80") (pin "1") (pinfunction "1_1") (pintype "unspecified"))
    )
    (net (code "151") (name "Net-(H8B-Pad1)") (class "Default")
      (node (ref "H8B") (pin "1") (pinfunction "1_1") (pintype "unspecified"))
      (node (ref "R71") (pin "2") (pinfunction "2_2") (pintype "unspecified"))
    )
    (net (code "152") (name "Net-(H8B-Pad2)") (class "Default")
      (node (ref "H8B") (pin "2") (pinfunction "2_2") (pintype "unspecified"))
      (node (ref "R72") (pin "2") (pinfunction "2_2") (pintype "unspecified"))
    )
    (net (code "153") (name "Net-(H8B-Pad3)") (class "Default")
      (node (ref "H8B") (pin "3") (pinfunction "3_3") (pintype "unspecified"))
      (node (ref "R73") (pin "2") (pinfunction "2_2") (pintype "unspecified"))
    )
    (net (code "154") (name "Net-(H8B-Pad4)") (class "Default")
      (node (ref "H8B") (pin "4") (pinfunction "4_4") (pintype "unspecified"))
      (node (ref "R74") (pin "2") (pinfunction "2_2") (pintype "unspecified"))
    )
    (net (code "155") (name "Net-(H8B-Pad5)") (class "Default")
      (node (ref "H8B") (pin "5") (pinfunction "5_5") (pintype "unspecified"))
      (node (ref "R75") (pin "2") (pinfunction "2_2") (pintype "unspecified"))
    )
    (net (code "156") (name "Net-(H8B-Pad6)") (class "Default")
      (node (ref "H8B") (pin "6") (pinfunction "6_6") (pintype "unspecified"))
      (node (ref "R76") (pin "2") (pinfunction "2_2") (pintype "unspecified"))
    )
    (net (code "157") (name "Net-(H8B-Pad7)") (class "Default")
      (node (ref "H8B") (pin "7") (pinfunction "7_7") (pintype "unspecified"))
      (node (ref "R77") (pin "2") (pinfunction "2_2") (pintype "unspecified"))
    )
    (net (code "158") (name "Net-(H8B-Pad8)") (class "Default")
      (node (ref "H8B") (pin "8") (pinfunction "8_8") (pintype "unspecified"))
      (node (ref "R78") (pin "2") (pinfunction "2_2") (pintype "unspecified"))
    )
    (net (code "159") (name "Net-(H8B-Pad9)") (class "Default")
      (node (ref "H8B") (pin "9") (pinfunction "9_9") (pintype "unspecified"))
      (node (ref "R79") (pin "2") (pinfunction "2_2") (pintype "unspecified"))
    )
    (net (code "160") (name "Net-(H8B-Pad10)") (class "Default")
      (node (ref "H8B") (pin "10") (pinfunction "10_10") (pintype "unspecified"))
      (node (ref "R80") (pin "2") (pinfunction "2_2") (pintype "unspecified"))
    )
    (net (code "161") (name "Net-(H9A-Pad1)") (class "Default")
      (node (ref "H9A") (pin "1") (pinfunction "1_1") (pintype "unspecified"))
      (node (ref "R81") (pin "1") (pinfunction "1_1") (pintype "unspecified"))
    )
    (net (code "162") (name "Net-(H9A-Pad2)") (class "Default")
      (node (ref "H9A") (pin "2") (pinfunction "2_2") (pintype "unspecified"))
      (node (ref "R82") (pin "1") (pinfunction "1_1") (pintype "unspecified"))
    )
    (net (code "163") (name "Net-(H9A-Pad3)") (class "Default")
      (node (ref "H9A") (pin "3") (pinfunction "3_3") (pintype "unspecified"))
      (node (ref "R83") (pin "1") (pinfunction "1_1") (pintype "unspecified"))
    )
    (net (code "164") (name "Net-(H9A-Pad4)") (class "Default")
      (node (ref "H9A") (pin "4") (pinfunction "4_4") (pintype "unspecified"))
      (node (ref "R84") (pin "1") (pinfunction "1_1") (pintype "unspecified"))
    )
    (net (code "165") (name "Net-(H9A-Pad5)") (class "Default")
      (node (ref "H9A") (pin "5") (pinfunction "5_5") (pintype "unspecified"))
      (node (ref "R85") (pin "1") (pinfunction "1_1") (pintype "unspecified"))
    )
    (net (code "166") (name "Net-(H9A-Pad6)") (class "Default")
      (node (ref "H9A") (pin "6") (pinfunction "6_6") (pintype "unspecified"))
      (node (ref "R86") (pin "1") (pinfunction "1_1") (pintype "unspecified"))
    )
    (net (code "167") (name "Net-(H9A-Pad7)") (class "Default")
      (node (ref "H9A") (pin "7") (pinfunction "7_7") (pintype "unspecified"))
      (node (ref "R87") (pin "1") (pinfunction "1_1") (pintype "unspecified"))
    )
    (net (code "168") (name "Net-(H9A-Pad8)") (class "Default")
      (node (ref "H9A") (pin "8") (pinfunction "8_8") (pintype "unspecified"))
      (node (ref "R88") (pin "1") (pinfunction "1_1") (pintype "unspecified"))
    )
    (net (code "169") (name "Net-(H9A-Pad9)") (class "Default")
      (node (ref "H9A") (pin "9") (pinfunction "9_9") (pintype "unspecified"))
      (node (ref "R89") (pin "1") (pinfunction "1_1") (pintype "unspecified"))
    )
    (net (code "170") (name "Net-(H9A-Pad10)") (class "Default")
      (node (ref "H9A") (pin "10") (pinfunction "10_10") (pintype "unspecified"))
      (node (ref "R90") (pin "1") (pinfunction "1_1") (pintype "unspecified"))
    )
    (net (code "171") (name "Net-(H9B-Pad1)") (class "Default")
      (node (ref "H9B") (pin "1") (pinfunction "1_1") (pintype "unspecified"))
      (node (ref "R81") (pin "2") (pinfunction "2_2") (pintype "unspecified"))
    )
    (net (code "172") (name "Net-(H9B-Pad2)") (class "Default")
      (node (ref "H9B") (pin "2") (pinfunction "2_2") (pintype "unspecified"))
      (node (ref "R82") (pin "2") (pinfunction "2_2") (pintype "unspecified"))
    )
    (net (code "173") (name "Net-(H9B-Pad3)") (class "Default")
      (node (ref "H9B") (pin "3") (pinfunction "3_3") (pintype "unspecified"))
      (node (ref "R83") (pin "2") (pinfunction "2_2") (pintype "unspecified"))
    )
    (net (code "174") (name "Net-(H9B-Pad4)") (class "Default")
      (node (ref "H9B") (pin "4") (pinfunction "4_4") (pintype "unspecified"))
      (node (ref "R84") (pin "2") (pinfunction "2_2") (pintype "unspecified"))
    )
    (net (code "175") (name "Net-(H9B-Pad5)") (class "Default")
      (node (ref "H9B") (pin "5") (pinfunction "5_5") (pintype "unspecified"))
      (node (ref "R85") (pin "2") (pinfunction "2_2") (pintype "unspecified"))
    )
    (net (code "176") (name "Net-(H9B-Pad6)") (class "Default")
      (node (ref "H9B") (pin "6") (pinfunction "6_6") (pintype "unspecified"))
      (node (ref "R86") (pin "2") (pinfunction "2_2") (pintype "unspecified"))
    )
    (net (code "177") (name "Net-(H9B-Pad7)") (class "Default")
      (node (ref "H9B") (pin "7") (pinfunction "7_7") (pintype "unspecified"))
      (node (ref "R87") (pin "2") (pinfunction "2_2") (pintype "unspecified"))
    )
    (net (code "178") (name "Net-(H9B-Pad8)") (class "Default")
      (node (ref "H9B") (pin "8") (pinfunction "8_8") (pintype "unspecified"))
      (node (ref "R88") (pin "2") (pinfunction "2_2") (pintype "unspecified"))
    )
    (net (code "179") (name "Net-(H9B-Pad9)") (class "Default")
      (node (ref "H9B") (pin "9") (pinfunction "9_9") (pintype "unspecified"))
      (node (ref "R89") (pin "2") (pinfunction "2_2") (pintype "unspecified"))
    )
    (net (code "180") (name "Net-(H9B-Pad10)") (class "Default")
      (node (ref "H9B") (pin "10") (pinfunction "10_10") (pintype "unspecified"))
      (node (ref "R90") (pin "2") (pinfunction "2_2") (pintype "unspecified"))
    )
    (net (code "181") (name "Net-(H10A-Pad1)") (class "Default")
      (node (ref "H10A") (pin "1") (pinfunction "1_1") (pintype "unspecified"))
      (node (ref "R91") (pin "1") (pinfunction "1_1") (pintype "unspecified"))
    )
    (net (code "182") (name "Net-(H10A-Pad2)") (class "Default")
      (node (ref "H10A") (pin "2") (pinfunction "2_2") (pintype "unspecified"))
      (node (ref "R92") (pin "1") (pinfunction "1_1") (pintype "unspecified"))
    )
    (net (code "183") (name "Net-(H10A-Pad3)") (class "Default")
      (node (ref "H10A") (pin "3") (pinfunction "3_3") (pintype "unspecified"))
      (node (ref "R93") (pin "1") (pinfunction "1_1") (pintype "unspecified"))
    )
    (net (code "184") (name "Net-(H10A-Pad4)") (class "Default")
      (node (ref "H10A") (pin "4") (pinfunction "4_4") (pintype "unspecified"))
      (node (ref "R94") (pin "1") (pinfunction "1_1") (pintype "unspecified"))
    )
    (net (code "185") (name "Net-(H10A-Pad5)") (class "Default")
      (node (ref "H10A") (pin "5") (pinfunction "5_5") (pintype "unspecified"))
      (node (ref "R95") (pin "1") (pinfunction "1_1") (pintype "unspecified"))
    )
    (net (code "186") (name "Net-(H10A-Pad6)") (class "Default")
      (node (ref "H10A") (pin "6") (pinfunction "6_6") (pintype "unspecified"))
      (node (ref "R96") (pin "1") (pinfunction "1_1") (pintype "unspecified"))
    )
    (net (code "187") (name "Net-(H10A-Pad7)") (class "Default")
      (node (ref "H10A") (pin "7") (pinfunction "7_7") (pintype "unspecified"))
      (node (ref "R97") (pin "1") (pinfunction "1_1") (pintype "unspecified"))
    )
    (net (code "188") (name "Net-(H10A-Pad8)") (class "Default")
      (node (ref "H10A") (pin "8") (pinfunction "8_8") (pintype "unspecified"))
      (node (ref "R98") (pin "1") (pinfunction "1_1") (pintype "unspecified"))
    )
    (net (code "189") (name "Net-(H10A-Pad9)") (class "Default")
      (node (ref "H10A") (pin "9") (pinfunction "9_9") (pintype "unspecified"))
      (node (ref "R99") (pin "1") (pinfunction "1_1") (pintype "unspecified"))
    )
    (net (code "190") (name "Net-(H10A-Pad10)") (class "Default")
      (node (ref "H10A") (pin "10") (pinfunction "10_10") (pintype "unspecified"))
      (node (ref "R100") (pin "1") (pinfunction "1_1") (pintype "unspecified"))
    )
    (net (code "191") (name "Net-(H10B-Pad1)") (class "Default")
      (node (ref "H10B") (pin "1") (pinfunction "1_1") (pintype "unspecified"))
      (node (ref "R91") (pin "2") (pinfunction "2_2") (pintype "unspecified"))
    )
    (net (code "192") (name "Net-(H10B-Pad2)") (class "Default")
      (node (ref "H10B") (pin "2") (pinfunction "2_2") (pintype "unspecified"))
      (node (ref "R92") (pin "2") (pinfunction "2_2") (pintype "unspecified"))
    )
    (net (code "193") (name "Net-(H10B-Pad3)") (class "Default")
      (node (ref "H10B") (pin "3") (pinfunction "3_3") (pintype "unspecified"))
      (node (ref "R93") (pin "2") (pinfunction "2_2") (pintype "unspecified"))
    )
    (net (code "194") (name "Net-(H10B-Pad4)") (class "Default")
      (node (ref "H10B") (pin "4") (pinfunction "4_4") (pintype "unspecified"))
      (node (ref "R94") (pin "2") (pinfunction "2_2") (pintype "unspecified"))
    )
    (net (code "195") (name "Net-(H10B-Pad5)") (class "Default")
      (node (ref "H10B") (pin "5") (pinfunction "5_5") (pintype "unspecified"))
      (node (ref "R95") (pin "2") (pinfunction "2_2") (pintype "unspecified"))
    )
    (net (code "196") (name "Net-(H10B-Pad6)") (class "Default")
      (node (ref "H10B") (pin "6") (pinfunction "6_6") (pintype "unspecified"))
      (node (ref "R96") (pin "2") (pinfunction "2_2") (pintype "unspecified"))
    )
    (net (code "197") (name "Net-(H10B-Pad7)") (class "Default")
      (node (ref "H10B") (pin "7") (pinfunction "7_7") (pintype "unspecified"))
      (node (ref "R97") (pin "2") (pinfunction "2_2") (pintype "unspecified"))
    )
    (net (code "198") (name "Net-(H10B-Pad8)") (class "Default")
      (node (ref "H10B") (pin "8") (pinfunction "8_8") (pintype "unspecified"))
      (node (ref "R98") (pin "2") (pinfunction "2_2") (pintype "unspecified"))
    )
    (net (code "199") (name "Net-(H10B-Pad9)") (class "Default")
      (node (ref "H10B") (pin "9") (pinfunction "9_9") (pintype "unspecified"))
      (node (ref "R99") (pin "2") (pinfunction "2_2") (pintype "unspecified"))
    )
    (net (code "200") (name "Net-(H10B-Pad10)") (class "Default")
      (node (ref "H10B") (pin "10") (pinfunction "10_10") (pintype "unspecified"))
      (node (ref "R100") (pin "2") (pinfunction "2_2") (pintype "unspecified"))
    )
    (net (code "201") (name "Net-(H11A-Pad1)") (class "Default")
      (node (ref "H11A") (pin "1") (pinfunction "1_1") (pintype "unspecified"))
      (node (ref "R101") (pin "1") (pinfunction "1_1") (pintype "unspecified"))
    )
    (net (code "202") (name "Net-(H11A-Pad2)") (class "Default")
      (node (ref "H11A") (pin "2") (pinfunction "2_2") (pintype "unspecified"))
      (node (ref "R102") (pin "1") (pinfunction "1_1") (pintype "unspecified"))
    )
    (net (code "203") (name "Net-(H11A-Pad3)") (class "Default")
      (node (ref "H11A") (pin "3") (pinfunction "3_3") (pintype "unspecified"))
      (node (ref "R103") (pin "1") (pinfunction "1_1") (pintype "unspecified"))
    )
    (net (code "204") (name "Net-(H11A-Pad4)") (class "Default")
      (node (ref "H11A") (pin "4") (pinfunction "4_4") (pintype "unspecified"))
      (node (ref "R104") (pin "1") (pinfunction "1_1") (pintype "unspecified"))
    )
    (net (code "205") (name "Net-(H11A-Pad5)") (class "Default")
      (node (ref "H11A") (pin "5") (pinfunction "5_5") (pintype "unspecified"))
      (node (ref "R105") (pin "1") (pinfunction "1_1") (pintype "unspecified"))
    )
    (net (code "206") (name "Net-(H11A-Pad6)") (class "Default")
      (node (ref "H11A") (pin "6") (pinfunction "6_6") (pintype "unspecified"))
      (node (ref "R106") (pin "1") (pinfunction "1_1") (pintype "unspecified"))
    )
    (net (code "207") (name "Net-(H11A-Pad7)") (class "Default")
      (node (ref "H11A") (pin "7") (pinfunction "7_7") (pintype "unspecified"))
      (node (ref "R107") (pin "1") (pinfunction "1_1") (pintype "unspecified"))
    )
    (net (code "208") (name "Net-(H11A-Pad8)") (class "Default")
      (node (ref "H11A") (pin "8") (pinfunction "8_8") (pintype "unspecified"))
      (node (ref "R108") (pin "1") (pinfunction "1_1") (pintype "unspecified"))
    )
    (net (code "209") (name "Net-(H11A-Pad9)") (class "Default")
      (node (ref "H11A") (pin "9") (pinfunction "9_9") (pintype "unspecified"))
      (node (ref "R109") (pin "1") (pinfunction "1_1") (pintype "unspecified"))
    )
    (net (code "210") (name "Net-(H11A-Pad10)") (class "Default")
      (node (ref "H11A") (pin "10") (pinfunction "10_10") (pintype "unspecified"))
      (node (ref "R110") (pin "1") (pinfunction "1_1") (pintype "unspecified"))
    )
    (net (code "211") (name "Net-(H11B-Pad1)") (class "Default")
      (node (ref "H11B") (pin "1") (pinfunction "1_1") (pintype "unspecified"))
      (node (ref "R101") (pin "2") (pinfunction "2_2") (pintype "unspecified"))
    )
    (net (code "212") (name "Net-(H11B-Pad2)") (class "Default")
      (node (ref "H11B") (pin "2") (pinfunction "2_2") (pintype "unspecified"))
      (node (ref "R102") (pin "2") (pinfunction "2_2") (pintype "unspecified"))
    )
    (net (code "213") (name "Net-(H11B-Pad3)") (class "Default")
      (node (ref "H11B") (pin "3") (pinfunction "3_3") (pintype "unspecified"))
      (node (ref "R103") (pin "2") (pinfunction "2_2") (pintype "unspecified"))
    )
    (net (code "214") (name "Net-(H11B-Pad4)") (class "Default")
      (node (ref "H11B") (pin "4") (pinfunction "4_4") (pintype "unspecified"))
      (node (ref "R104") (pin "2") (pinfunction "2_2") (pintype "unspecified"))
    )
    (net (code "215") (name "Net-(H11B-Pad5)") (class "Default")
      (node (ref "H11B") (pin "5") (pinfunction "5_5") (pintype "unspecified"))
      (node (ref "R105") (pin "2") (pinfunction "2_2") (pintype "unspecified"))
    )
    (net (code "216") (name "Net-(H11B-Pad6)") (class "Default")
      (node (ref "H11B") (pin "6") (pinfunction "6_6") (pintype "unspecified"))
      (node (ref "R106") (pin "2") (pinfunction "2_2") (pintype "unspecified"))
    )
    (net (code "217") (name "Net-(H11B-Pad7)") (class "Default")
      (node (ref "H11B") (pin "7") (pinfunction "7_7") (pintype "unspecified"))
      (node (ref "R107") (pin "2") (pinfunction "2_2") (pintype "unspecified"))
    )
    (net (code "218") (name "Net-(H11B-Pad8)") (class "Default")
      (node (ref "H11B") (pin "8") (pinfunction "8_8") (pintype "unspecified"))
      (node (ref "R108") (pin "2") (pinfunction "2_2") (pintype "unspecified"))
    )
    (net (code "219") (name "Net-(H11B-Pad9)") (class "Default")
      (node (ref "H11B") (pin "9") (pinfunction "9_9") (pintype "unspecified"))
      (node (ref "R109") (pin "2") (pinfunction "2_2") (pintype "unspecified"))
    )
    (net (code "220") (name "Net-(H11B-Pad10)") (class "Default")
      (node (ref "H11B") (pin "10") (pinfunction "10_10") (pintype "unspecified"))
      (node (ref "R110") (pin "2") (pinfunction "2_2") (pintype "unspecified"))
    )
    (net (code "221") (name "Net-(H12A-Pad1)") (class "Default")
      (node (ref "H12A") (pin "1") (pinfunction "1_1") (pintype "unspecified"))
      (node (ref "R111") (pin "1") (pinfunction "1_1") (pintype "unspecified"))
    )
    (net (code "222") (name "Net-(H12A-Pad2)") (class "Default")
      (node (ref "H12A") (pin "2") (pinfunction "2_2") (pintype "unspecified"))
      (node (ref "R112") (pin "1") (pinfunction "1_1") (pintype "unspecified"))
    )
    (net (code "223") (name "Net-(H12A-Pad3)") (class "Default")
      (node (ref "H12A") (pin "3") (pinfunction "3_3") (pintype "unspecified"))
      (node (ref "R113") (pin "1") (pinfunction "1_1") (pintype "unspecified"))
    )
    (net (code "224") (name "Net-(H12A-Pad4)") (class "Default")
      (node (ref "H12A") (pin "4") (pinfunction "4_4") (pintype "unspecified"))
      (node (ref "R114") (pin "1") (pinfunction "1_1") (pintype "unspecified"))
    )
    (net (code "225") (name "Net-(H12A-Pad5)") (class "Default")
      (node (ref "H12A") (pin "5") (pinfunction "5_5") (pintype "unspecified"))
      (node (ref "R115") (pin "1") (pinfunction "1_1") (pintype "unspecified"))
    )
    (net (code "226") (name "Net-(H12A-Pad6)") (class "Default")
      (node (ref "H12A") (pin "6") (pinfunction "6_6") (pintype "unspecified"))
      (node (ref "R116") (pin "1") (pinfunction "1_1") (pintype "unspecified"))
    )
    (net (code "227") (name "Net-(H12A-Pad7)") (class "Default")
      (node (ref "H12A") (pin "7") (pinfunction "7_7") (pintype "unspecified"))
      (node (ref "R117") (pin "1") (pinfunction "1_1") (pintype "unspecified"))
    )
    (net (code "228") (name "Net-(H12A-Pad8)") (class "Default")
      (node (ref "H12A") (pin "8") (pinfunction "8_8") (pintype "unspecified"))
      (node (ref "R118") (pin "1") (pinfunction "1_1") (pintype "unspecified"))
    )
    (net (code "229") (name "Net-(H12A-Pad9)") (class "Default")
      (node (ref "H12A") (pin "9") (pinfunction "9_9") (pintype "unspecified"))
      (node (ref "R119") (pin "1") (pinfunction "1_1") (pintype "unspecified"))
    )
    (net (code "230") (name "Net-(H12A-Pad10)") (class "Default")
      (node (ref "H12A") (pin "10") (pinfunction "10_10") (pintype "unspecified"))
      (node (ref "R120") (pin "1") (pinfunction "1_1") (pintype "unspecified"))
    )
    (net (code "231") (name "Net-(H12B-Pad1)") (class "Default")
      (node (ref "H12B") (pin "1") (pinfunction "1_1") (pintype "unspecified"))
      (node (ref "R111") (pin "2") (pinfunction "2_2") (pintype "unspecified"))
    )
    (net (code "232") (name "Net-(H12B-Pad2)") (class "Default")
      (node (ref "H12B") (pin "2") (pinfunction "2_2") (pintype "unspecified"))
      (node (ref "R112") (pin "2") (pinfunction "2_2") (pintype "unspecified"))
    )
    (net (code "233") (name "Net-(H12B-Pad3)") (class "Default")
      (node (ref "H12B") (pin "3") (pinfunction "3_3") (pintype "unspecified"))
      (node (ref "R113") (pin "2") (pinfunction "2_2") (pintype "unspecified"))
    )
    (net (code "234") (name "Net-(H12B-Pad4)") (class "Default")
      (node (ref "H12B") (pin "4") (pinfunction "4_4") (pintype "unspecified"))
      (node (ref "R114") (pin "2") (pinfunction "2_2") (pintype "unspecified"))
    )
    (net (code "235") (name "Net-(H12B-Pad5)") (class "Default")
      (node (ref "H12B") (pin "5") (pinfunction "5_5") (pintype "unspecified"))
      (node (ref "R115") (pin "2") (pinfunction "2_2") (pintype "unspecified"))
    )
    (net (code "236") (name "Net-(H12B-Pad6)") (class "Default")
      (node (ref "H12B") (pin "6") (pinfunction "6_6") (pintype "unspecified"))
      (node (ref "R116") (pin "2") (pinfunction "2_2") (pintype "unspecified"))
    )
    (net (code "237") (name "Net-(H12B-Pad7)") (class "Default")
      (node (ref "H12B") (pin "7") (pinfunction "7_7") (pintype "unspecified"))
      (node (ref "R117") (pin "2") (pinfunction "2_2") (pintype "unspecified"))
    )
    (net (code "238") (name "Net-(H12B-Pad8)") (class "Default")
      (node (ref "H12B") (pin "8") (pinfunction "8_8") (pintype "unspecified"))
      (node (ref "R118") (pin "2") (pinfunction "2_2") (pintype "unspecified"))
    )
    (net (code "239") (name "Net-(H12B-Pad9)") (class "Default")
      (node (ref "H12B") (pin "9") (pinfunction "9_9") (pintype "unspecified"))
      (node (ref "R119") (pin "2") (pinfunction "2_2") (pintype "unspecified"))
    )
    (net (code "240") (name "Net-(H12B-Pad10)") (class "Default")
      (node (ref "H12B") (pin "10") (pinfunction "10_10") (pintype "unspecified"))
      (node (ref "R120") (pin "2") (pinfunction "2_2") (pintype "unspecified"))
    )
  )
)
